# BRIDGE.net
KiCad netlist of a schematic drawn in Altium Designer
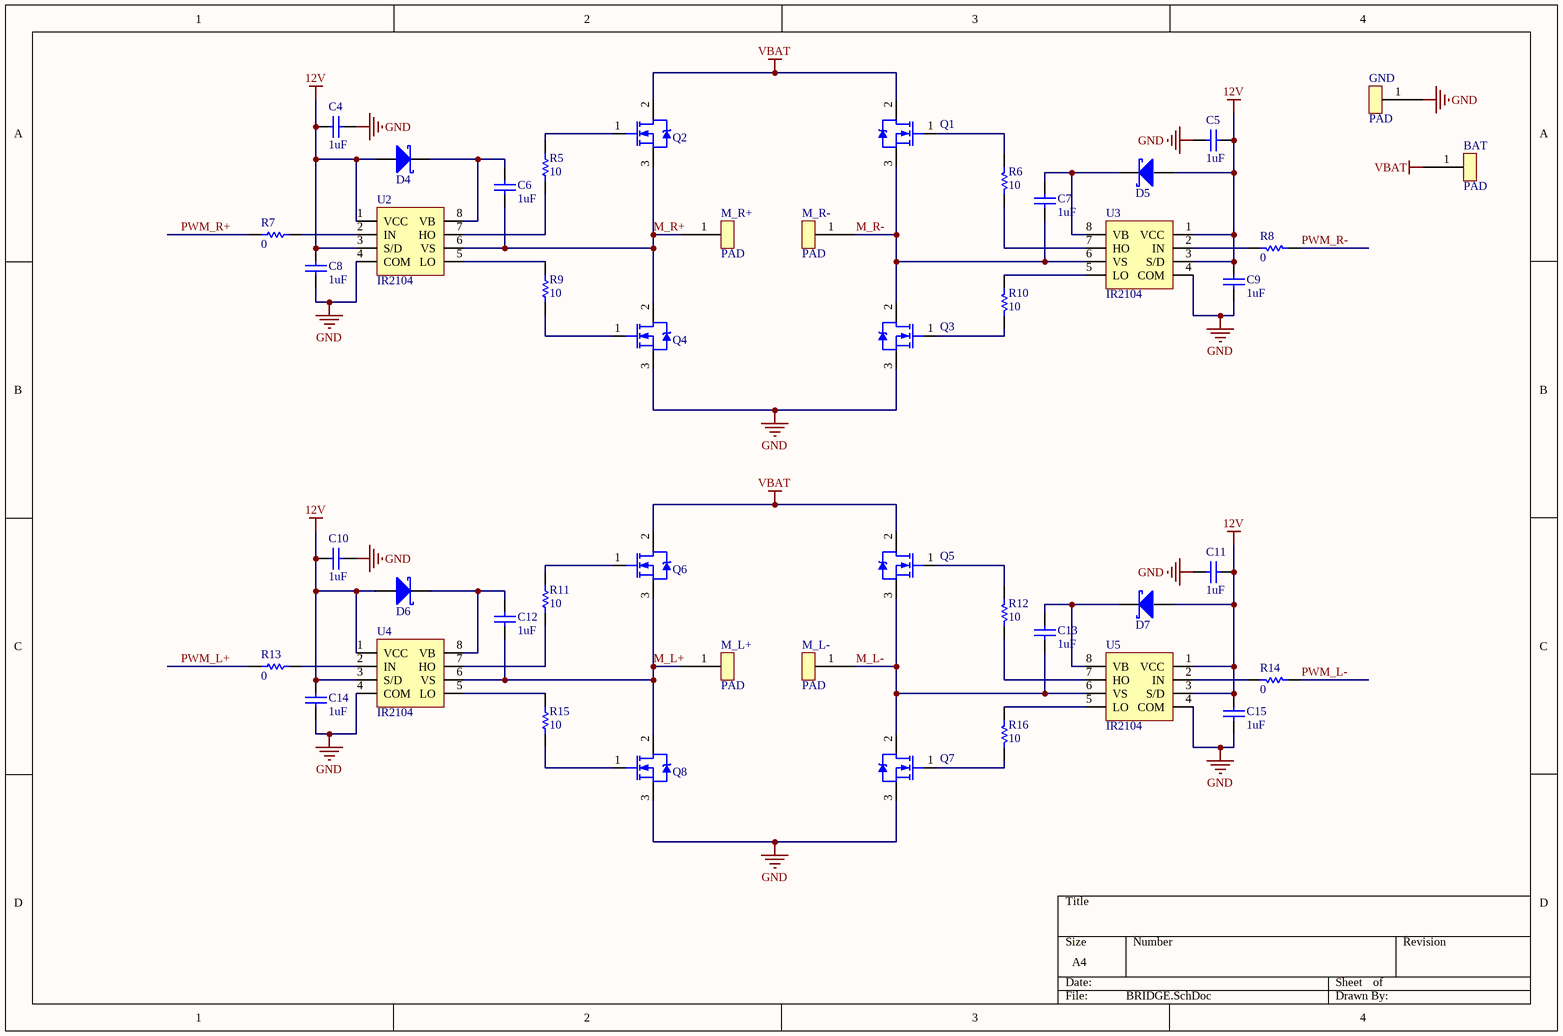
[diagram p0: BRIDGE.SchDoc]

(export (version "E")
  (design (tool "Eeschema 10.0.6"))
  (components
    (comp (ref "BAT") (value "PAD") (footprint "PAD_BIG") (libsource (lib "My Footprint") (part "PAD")))
    (comp (ref "C4")
      (value "1uF")
      (footprint "C1210")
      (description "Capacitor")
      (fields (field (name "PUBLISHER") "Altium Limited"))
      (libsource (lib "My Footprint") (part "CAP"))
    )
    (comp (ref "C5")
      (value "1uF")
      (footprint "C1210")
      (description "Capacitor")
      (fields (field (name "PUBLISHER") "Altium Limited"))
      (libsource (lib "My Footprint") (part "CAP"))
    )
    (comp (ref "C6")
      (value "1uF")
      (footprint "0603_C")
      (description "Capacitor")
      (fields (field (name "PUBLISHER") "Altium Limited"))
      (libsource (lib "My Footprint") (part "CAP"))
    )
    (comp (ref "C7")
      (value "1uF")
      (footprint "0603_C")
      (description "Capacitor")
      (fields (field (name "PUBLISHER") "Altium Limited"))
      (libsource (lib "My Footprint") (part "CAP"))
    )
    (comp (ref "C8")
      (value "1uF")
      (footprint "0603_C")
      (description "Capacitor")
      (fields (field (name "PUBLISHER") "Altium Limited"))
      (libsource (lib "My Footprint") (part "CAP"))
    )
    (comp (ref "C9")
      (value "1uF")
      (footprint "0603_C")
      (description "Capacitor")
      (fields (field (name "PUBLISHER") "Altium Limited"))
      (libsource (lib "My Footprint") (part "CAP"))
    )
    (comp (ref "C10")
      (value "1uF")
      (footprint "C1210")
      (description "Capacitor")
      (fields (field (name "PUBLISHER") "Altium Limited"))
      (libsource (lib "My Footprint") (part "CAP"))
    )
    (comp (ref "C11")
      (value "1uF")
      (footprint "C1210")
      (description "Capacitor")
      (fields (field (name "PUBLISHER") "Altium Limited"))
      (libsource (lib "My Footprint") (part "CAP"))
    )
    (comp (ref "C12")
      (value "1uF")
      (footprint "0603_C")
      (description "Capacitor")
      (fields (field (name "PUBLISHER") "Altium Limited"))
      (libsource (lib "My Footprint") (part "CAP"))
    )
    (comp (ref "C13")
      (value "1uF")
      (footprint "0603_C")
      (description "Capacitor")
      (fields (field (name "PUBLISHER") "Altium Limited"))
      (libsource (lib "My Footprint") (part "CAP"))
    )
    (comp (ref "C14")
      (value "1uF")
      (footprint "0603_C")
      (description "Capacitor")
      (fields (field (name "PUBLISHER") "Altium Limited"))
      (libsource (lib "My Footprint") (part "CAP"))
    )
    (comp (ref "C15")
      (value "1uF")
      (footprint "0603_C")
      (description "Capacitor")
      (fields (field (name "PUBLISHER") "Altium Limited"))
      (libsource (lib "My Footprint") (part "CAP"))
    )
    (comp (ref "D4")
      (value "Diode Schottky")
      (footprint "DO-214AC")
      (libsource (lib "通用驱动") (part "Diode Schottky"))
    )
    (comp (ref "D5")
      (value "Diode Schottky")
      (footprint "DO-214AC")
      (libsource (lib "通用驱动") (part "Diode Schottky"))
    )
    (comp (ref "D6")
      (value "Diode Schottky")
      (footprint "DO-214AC")
      (libsource (lib "通用驱动") (part "Diode Schottky"))
    )
    (comp (ref "D7")
      (value "Diode Schottky")
      (footprint "DO-214AC")
      (libsource (lib "通用驱动") (part "Diode Schottky"))
    )
    (comp (ref "GND") (value "PAD") (footprint "PAD_BIG") (libsource (lib "") (part "PAD_1")))
    (comp (ref "M_L+") (value "PAD") (footprint "PAD_BIG") (libsource (lib "My Footprint") (part "PAD")))
    (comp (ref "M_L-") (value "PAD") (footprint "PAD_BIG") (libsource (lib "") (part "PAD_1")))
    (comp (ref "M_R+") (value "PAD") (footprint "PAD_BIG") (libsource (lib "My Footprint") (part "PAD")))
    (comp (ref "M_R-") (value "PAD") (footprint "PAD_BIG") (libsource (lib "") (part "PAD_1")))
    (comp (ref "Q1") (value "MOSFET N") (footprint "TO-252AA") (libsource (lib "通用驱动") (part "MOSFET N")))
    (comp (ref "Q2") (value "MOSFET N") (footprint "TO-252AA") (libsource (lib "通用驱动") (part "MOSFET N")))
    (comp (ref "Q3") (value "MOSFET N") (footprint "TO-252AA") (libsource (lib "通用驱动") (part "MOSFET N")))
    (comp (ref "Q4") (value "MOSFET N") (footprint "TO-252AA") (libsource (lib "通用驱动") (part "MOSFET N")))
    (comp (ref "Q5") (value "MOSFET N") (footprint "TO-252AA") (libsource (lib "通用驱动") (part "MOSFET N")))
    (comp (ref "Q6") (value "MOSFET N") (footprint "TO-252AA") (libsource (lib "通用驱动") (part "MOSFET N")))
    (comp (ref "Q7") (value "MOSFET N") (footprint "TO-252AA") (libsource (lib "通用驱动") (part "MOSFET N")))
    (comp (ref "Q8") (value "MOSFET N") (footprint "TO-252AA") (libsource (lib "通用驱动") (part "MOSFET N")))
    (comp (ref "R5")
      (value "10")
      (footprint "0603_R")
      (description "Resistor")
      (fields (field (name "PUBLISHER") "Altium Limited"))
      (libsource (lib "My Footprint") (part "RES"))
    )
    (comp (ref "R6")
      (value "10")
      (footprint "0603_R")
      (description "Resistor")
      (fields (field (name "PUBLISHER") "Altium Limited"))
      (libsource (lib "My Footprint") (part "RES"))
    )
    (comp (ref "R7")
      (value "0")
      (footprint "0603_R")
      (description "Resistor")
      (fields (field (name "PUBLISHER") "Altium Limited"))
      (libsource (lib "My Footprint") (part "RES"))
    )
    (comp (ref "R8")
      (value "0")
      (footprint "0603_R")
      (description "Resistor")
      (fields (field (name "PUBLISHER") "Altium Limited"))
      (libsource (lib "My Footprint") (part "RES"))
    )
    (comp (ref "R9")
      (value "10")
      (footprint "0603_R")
      (description "Resistor")
      (fields (field (name "PUBLISHER") "Altium Limited"))
      (libsource (lib "My Footprint") (part "RES"))
    )
    (comp (ref "R10")
      (value "10")
      (footprint "0603_R")
      (description "Resistor")
      (fields (field (name "PUBLISHER") "Altium Limited"))
      (libsource (lib "My Footprint") (part "RES"))
    )
    (comp (ref "R11")
      (value "10")
      (footprint "0603_R")
      (description "Resistor")
      (fields (field (name "PUBLISHER") "Altium Limited"))
      (libsource (lib "My Footprint") (part "RES"))
    )
    (comp (ref "R12")
      (value "10")
      (footprint "0603_R")
      (description "Resistor")
      (fields (field (name "PUBLISHER") "Altium Limited"))
      (libsource (lib "My Footprint") (part "RES"))
    )
    (comp (ref "R13")
      (value "0")
      (footprint "0603_R")
      (description "Resistor")
      (fields (field (name "PUBLISHER") "Altium Limited"))
      (libsource (lib "My Footprint") (part "RES"))
    )
    (comp (ref "R14")
      (value "0")
      (footprint "0603_R")
      (description "Resistor")
      (fields (field (name "PUBLISHER") "Altium Limited"))
      (libsource (lib "My Footprint") (part "RES"))
    )
    (comp (ref "R15")
      (value "10")
      (footprint "0603_R")
      (description "Resistor")
      (fields (field (name "PUBLISHER") "Altium Limited"))
      (libsource (lib "My Footprint") (part "RES"))
    )
    (comp (ref "R16")
      (value "10")
      (footprint "0603_R")
      (description "Resistor")
      (fields (field (name "PUBLISHER") "Altium Limited"))
      (libsource (lib "My Footprint") (part "RES"))
    )
    (comp (ref "U2")
      (value "IR2104")
      (footprint "SOIC-8")
      (description "半桥驱动器")
      (libsource (lib "通用驱动") (part "IR2104"))
    )
    (comp (ref "U3")
      (value "IR2104")
      (footprint "SOIC-8")
      (description "半桥驱动器")
      (libsource (lib "") (part "IR2104_1"))
    )
    (comp (ref "U4")
      (value "IR2104")
      (footprint "SOIC-8")
      (description "半桥驱动器")
      (libsource (lib "通用驱动") (part "IR2104"))
    )
    (comp (ref "U5")
      (value "IR2104")
      (footprint "SOIC-8")
      (description "半桥驱动器")
      (libsource (lib "") (part "IR2104_1"))
    )
  )
  (nets
    (net (code "1") (name "/M_L+") (class "Default")
      (node (ref "C12") (pin "1") (pinfunction "1_1") (pintype "passive"))
      (node (ref "M_L+") (pin "1") (pintype "passive"))
      (node (ref "Q6") (pin "3") (pinfunction "S_3") (pintype "passive"))
      (node (ref "Q8") (pin "2") (pinfunction "D_2") (pintype "passive"))
      (node (ref "U4") (pin "6") (pinfunction "VS_6") (pintype "passive"))
    )
    (net (code "2") (name "/M_L-") (class "Default")
      (node (ref "C13") (pin "1") (pinfunction "1_1") (pintype "passive"))
      (node (ref "M_L-") (pin "1") (pintype "passive"))
      (node (ref "Q5") (pin "3") (pinfunction "S_3") (pintype "passive"))
      (node (ref "Q7") (pin "2") (pinfunction "D_2") (pintype "passive"))
      (node (ref "U5") (pin "6") (pinfunction "VS_6") (pintype "passive"))
    )
    (net (code "3") (name "/M_R+") (class "Default")
      (node (ref "C6") (pin "1") (pinfunction "1_1") (pintype "passive"))
      (node (ref "M_R+") (pin "1") (pintype "passive"))
      (node (ref "Q2") (pin "3") (pinfunction "S_3") (pintype "passive"))
      (node (ref "Q4") (pin "2") (pinfunction "D_2") (pintype "passive"))
      (node (ref "U2") (pin "6") (pinfunction "VS_6") (pintype "passive"))
    )
    (net (code "4") (name "/M_R-") (class "Default")
      (node (ref "C7") (pin "1") (pinfunction "1_1") (pintype "passive"))
      (node (ref "M_R-") (pin "1") (pintype "passive"))
      (node (ref "Q1") (pin "3") (pinfunction "S_3") (pintype "passive"))
      (node (ref "Q3") (pin "2") (pinfunction "D_2") (pintype "passive"))
      (node (ref "U3") (pin "6") (pinfunction "VS_6") (pintype "passive"))
    )
    (net (code "5") (name "/PWM_L+") (class "Default")
      (node (ref "R13") (pin "1") (pinfunction "1_1") (pintype "passive"))
    )
    (net (code "6") (name "/PWM_L-") (class "Default")
      (node (ref "R14") (pin "1") (pinfunction "1_1") (pintype "passive"))
    )
    (net (code "7") (name "/PWM_R+") (class "Default")
      (node (ref "R7") (pin "1") (pinfunction "1_1") (pintype "passive"))
    )
    (net (code "8") (name "/PWM_R-") (class "Default")
      (node (ref "R8") (pin "1") (pinfunction "1_1") (pintype "passive"))
    )
    (net (code "9") (name "12V") (class "Default")
      (node (ref "C10") (pin "1") (pinfunction "1_1") (pintype "passive"))
      (node (ref "C11") (pin "2") (pinfunction "2_2") (pintype "passive"))
      (node (ref "C14") (pin "2") (pinfunction "2_2") (pintype "passive"))
      (node (ref "C15") (pin "2") (pinfunction "2_2") (pintype "passive"))
      (node (ref "C4") (pin "1") (pinfunction "1_1") (pintype "passive"))
      (node (ref "C5") (pin "2") (pinfunction "2_2") (pintype "passive"))
      (node (ref "C8") (pin "2") (pinfunction "2_2") (pintype "passive"))
      (node (ref "C9") (pin "2") (pinfunction "2_2") (pintype "passive"))
      (node (ref "D4") (pin "1") (pinfunction "A_1") (pintype "passive"))
      (node (ref "D5") (pin "1") (pinfunction "A_1") (pintype "passive"))
      (node (ref "D6") (pin "1") (pinfunction "A_1") (pintype "passive"))
      (node (ref "D7") (pin "1") (pinfunction "A_1") (pintype "passive"))
      (node (ref "U2") (pin "1") (pinfunction "VCC_1") (pintype "passive"))
      (node (ref "U2") (pin "3") (pinfunction "S/D_3") (pintype "passive"))
      (node (ref "U3") (pin "1") (pinfunction "VCC_1") (pintype "passive"))
      (node (ref "U3") (pin "3") (pinfunction "S/D_3") (pintype "passive"))
      (node (ref "U4") (pin "1") (pinfunction "VCC_1") (pintype "passive"))
      (node (ref "U4") (pin "3") (pinfunction "S/D_3") (pintype "passive"))
      (node (ref "U5") (pin "1") (pinfunction "VCC_1") (pintype "passive"))
      (node (ref "U5") (pin "3") (pinfunction "S/D_3") (pintype "passive"))
    )
    (net (code "10") (name "GND") (class "Default")
      (node (ref "C10") (pin "2") (pinfunction "2_2") (pintype "passive"))
      (node (ref "C11") (pin "1") (pinfunction "1_1") (pintype "passive"))
      (node (ref "C14") (pin "1") (pinfunction "1_1") (pintype "passive"))
      (node (ref "C15") (pin "1") (pinfunction "1_1") (pintype "passive"))
      (node (ref "C4") (pin "2") (pinfunction "2_2") (pintype "passive"))
      (node (ref "C5") (pin "1") (pinfunction "1_1") (pintype "passive"))
      (node (ref "C8") (pin "1") (pinfunction "1_1") (pintype "passive"))
      (node (ref "C9") (pin "1") (pinfunction "1_1") (pintype "passive"))
      (node (ref "GND") (pin "1") (pintype "passive"))
      (node (ref "Q3") (pin "3") (pinfunction "S_3") (pintype "passive"))
      (node (ref "Q4") (pin "3") (pinfunction "S_3") (pintype "passive"))
      (node (ref "Q7") (pin "3") (pinfunction "S_3") (pintype "passive"))
      (node (ref "Q8") (pin "3") (pinfunction "S_3") (pintype "passive"))
      (node (ref "U2") (pin "4") (pinfunction "COM_4") (pintype "passive"))
      (node (ref "U3") (pin "4") (pinfunction "COM_4") (pintype "passive"))
      (node (ref "U4") (pin "4") (pinfunction "COM_4") (pintype "passive"))
      (node (ref "U5") (pin "4") (pinfunction "COM_4") (pintype "passive"))
    )
    (net (code "11") (name "Net-(D4-K)") (class "Default")
      (node (ref "C6") (pin "2") (pinfunction "2_2") (pintype "passive"))
      (node (ref "D4") (pin "2") (pinfunction "K_2") (pintype "passive"))
      (node (ref "U2") (pin "8") (pinfunction "VB_8") (pintype "passive"))
    )
    (net (code "12") (name "Net-(D5-K)") (class "Default")
      (node (ref "C7") (pin "2") (pinfunction "2_2") (pintype "passive"))
      (node (ref "D5") (pin "2") (pinfunction "K_2") (pintype "passive"))
      (node (ref "U3") (pin "8") (pinfunction "VB_8") (pintype "passive"))
    )
    (net (code "13") (name "Net-(D6-K)") (class "Default")
      (node (ref "C12") (pin "2") (pinfunction "2_2") (pintype "passive"))
      (node (ref "D6") (pin "2") (pinfunction "K_2") (pintype "passive"))
      (node (ref "U4") (pin "8") (pinfunction "VB_8") (pintype "passive"))
    )
    (net (code "14") (name "Net-(D7-K)") (class "Default")
      (node (ref "C13") (pin "2") (pinfunction "2_2") (pintype "passive"))
      (node (ref "D7") (pin "2") (pinfunction "K_2") (pintype "passive"))
      (node (ref "U5") (pin "8") (pinfunction "VB_8") (pintype "passive"))
    )
    (net (code "15") (name "Net-(Q1-G)") (class "Default")
      (node (ref "Q1") (pin "1") (pinfunction "G_1") (pintype "passive"))
      (node (ref "R6") (pin "2") (pinfunction "2_2") (pintype "passive"))
    )
    (net (code "16") (name "Net-(Q2-G)") (class "Default")
      (node (ref "Q2") (pin "1") (pinfunction "G_1") (pintype "passive"))
      (node (ref "R5") (pin "2") (pinfunction "2_2") (pintype "passive"))
    )
    (net (code "17") (name "Net-(Q3-G)") (class "Default")
      (node (ref "Q3") (pin "1") (pinfunction "G_1") (pintype "passive"))
      (node (ref "R10") (pin "2") (pinfunction "2_2") (pintype "passive"))
    )
    (net (code "18") (name "Net-(Q4-G)") (class "Default")
      (node (ref "Q4") (pin "1") (pinfunction "G_1") (pintype "passive"))
      (node (ref "R9") (pin "2") (pinfunction "2_2") (pintype "passive"))
    )
    (net (code "19") (name "Net-(Q5-G)") (class "Default")
      (node (ref "Q5") (pin "1") (pinfunction "G_1") (pintype "passive"))
      (node (ref "R12") (pin "2") (pinfunction "2_2") (pintype "passive"))
    )
    (net (code "20") (name "Net-(Q6-G)") (class "Default")
      (node (ref "Q6") (pin "1") (pinfunction "G_1") (pintype "passive"))
      (node (ref "R11") (pin "2") (pinfunction "2_2") (pintype "passive"))
    )
    (net (code "21") (name "Net-(Q7-G)") (class "Default")
      (node (ref "Q7") (pin "1") (pinfunction "G_1") (pintype "passive"))
      (node (ref "R16") (pin "2") (pinfunction "2_2") (pintype "passive"))
    )
    (net (code "22") (name "Net-(Q8-G)") (class "Default")
      (node (ref "Q8") (pin "1") (pinfunction "G_1") (pintype "passive"))
      (node (ref "R15") (pin "2") (pinfunction "2_2") (pintype "passive"))
    )
    (net (code "23") (name "Net-(U2-HO)") (class "Default")
      (node (ref "R5") (pin "1") (pinfunction "1_1") (pintype "passive"))
      (node (ref "U2") (pin "7") (pinfunction "HO_7") (pintype "passive"))
    )
    (net (code "24") (name "Net-(U2-IN)") (class "Default")
      (node (ref "R7") (pin "2") (pinfunction "2_2") (pintype "passive"))
      (node (ref "U2") (pin "2") (pinfunction "IN_2") (pintype "passive"))
    )
    (net (code "25") (name "Net-(U2-LO)") (class "Default")
      (node (ref "R9") (pin "1") (pinfunction "1_1") (pintype "passive"))
      (node (ref "U2") (pin "5") (pinfunction "LO_5") (pintype "passive"))
    )
    (net (code "26") (name "Net-(U3-HO)") (class "Default")
      (node (ref "R6") (pin "1") (pinfunction "1_1") (pintype "passive"))
      (node (ref "U3") (pin "7") (pinfunction "HO_7") (pintype "passive"))
    )
    (net (code "27") (name "Net-(U3-IN)") (class "Default")
      (node (ref "R8") (pin "2") (pinfunction "2_2") (pintype "passive"))
      (node (ref "U3") (pin "2") (pinfunction "IN_2") (pintype "passive"))
    )
    (net (code "28") (name "Net-(U3-LO)") (class "Default")
      (node (ref "R10") (pin "1") (pinfunction "1_1") (pintype "passive"))
      (node (ref "U3") (pin "5") (pinfunction "LO_5") (pintype "passive"))
    )
    (net (code "29") (name "Net-(U4-HO)") (class "Default")
      (node (ref "R11") (pin "1") (pinfunction "1_1") (pintype "passive"))
      (node (ref "U4") (pin "7") (pinfunction "HO_7") (pintype "passive"))
    )
    (net (code "30") (name "Net-(U4-IN)") (class "Default")
      (node (ref "R13") (pin "2") (pinfunction "2_2") (pintype "passive"))
      (node (ref "U4") (pin "2") (pinfunction "IN_2") (pintype "passive"))
    )
    (net (code "31") (name "Net-(U4-LO)") (class "Default")
      (node (ref "R15") (pin "1") (pinfunction "1_1") (pintype "passive"))
      (node (ref "U4") (pin "5") (pinfunction "LO_5") (pintype "passive"))
    )
    (net (code "32") (name "Net-(U5-HO)") (class "Default")
      (node (ref "R12") (pin "1") (pinfunction "1_1") (pintype "passive"))
      (node (ref "U5") (pin "7") (pinfunction "HO_7") (pintype "passive"))
    )
    (net (code "33") (name "Net-(U5-IN)") (class "Default")
      (node (ref "R14") (pin "2") (pinfunction "2_2") (pintype "passive"))
      (node (ref "U5") (pin "2") (pinfunction "IN_2") (pintype "passive"))
    )
    (net (code "34") (name "Net-(U5-LO)") (class "Default")
      (node (ref "R16") (pin "1") (pinfunction "1_1") (pintype "passive"))
      (node (ref "U5") (pin "5") (pinfunction "LO_5") (pintype "passive"))
    )
    (net (code "35") (name "VBAT") (class "Default")
      (node (ref "BAT") (pin "1") (pintype "passive"))
      (node (ref "Q1") (pin "2") (pinfunction "D_2") (pintype "passive"))
      (node (ref "Q2") (pin "2") (pinfunction "D_2") (pintype "passive"))
      (node (ref "Q5") (pin "2") (pinfunction "D_2") (pintype "passive"))
      (node (ref "Q6") (pin "2") (pinfunction "D_2") (pintype "passive"))
    )
  )
)
